# test_board.net
KiCad netlist of a schematic drawn in EAGLE
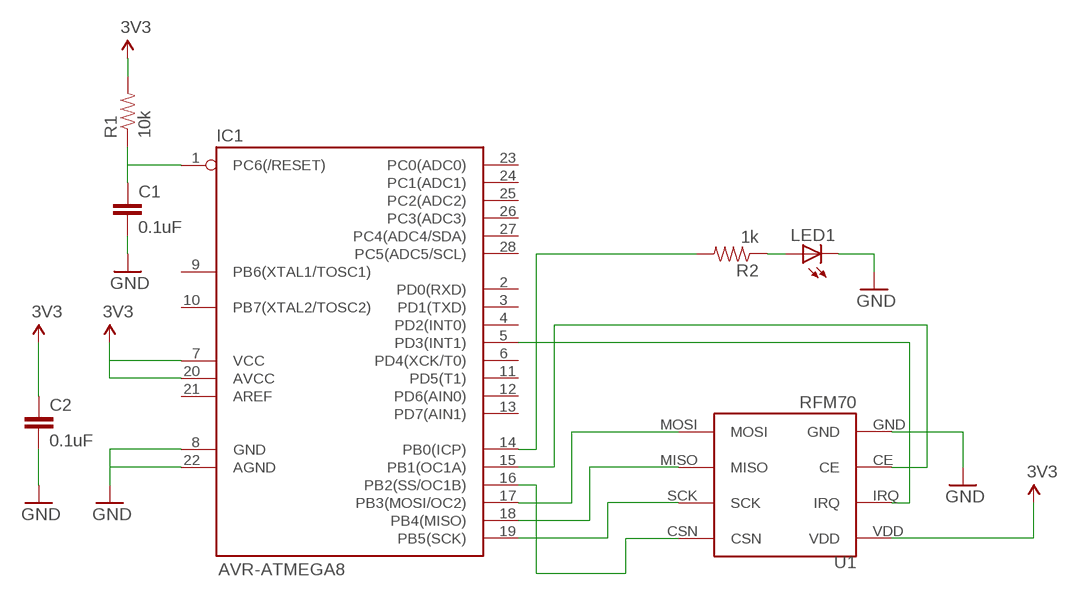
[diagram p0: schematic, sheet 1]

(export (version "E")
  (design (tool "Eeschema 10.0.6"))
  (components
    (comp (ref "C1")
      (value "0.1uF")
      (footprint "eagle-import:0603-CAP")
      (libsource (lib "eagle-import") (part "0.1UF-25V(+80/-20%)(0603)"))
    )
    (comp (ref "C2")
      (value "0.1uF")
      (footprint "eagle-import:0603-CAP")
      (libsource (lib "eagle-import") (part "0.1UF-25V(+80/-20%)(0603)"))
    )
    (comp (ref "IC1")
      (value "AVR-ATMEGA8")
      (footprint "eagle-import:DIL28-3")
      (libsource (lib "eagle-import") (part "AVR-MEGA8-PPTH"))
    )
    (comp (ref "LED1")
      (value "LED5MM")
      (footprint "eagle-import:LED5MM")
      (libsource (lib "eagle-import") (part "LED5MM"))
    )
    (comp (ref "R1")
      (value "10k")
      (footprint "eagle-import:0805")
      (libsource (lib "eagle-import") (part "0.75OHM-1/4W-1%(0805)"))
    )
    (comp (ref "R2")
      (value "1k")
      (footprint "eagle-import:0805")
      (libsource (lib "eagle-import") (part "0.75OHM-1/4W-1%(0805)"))
    )
    (comp (ref "U1")
      (value "RFM70")
      (footprint "eagle-import:RFM70")
      (libsource (lib "eagle-import") (part "RFM70"))
    )
  )
  (nets
    (net (code "1") (name "3V3") (class "Default")
      (node (ref "C2") (pin "1") (pinfunction "1_1") (pintype "passive"))
      (node (ref "IC1") (pin "20") (pinfunction "AVCC_20") (pintype "bidirectional"))
      (node (ref "IC1") (pin "7") (pinfunction "VCC_7") (pintype "bidirectional"))
      (node (ref "R1") (pin "2") (pinfunction "2_2") (pintype "passive"))
      (node (ref "U1") (pin "VDD") (pinfunction "VDD_VDD") (pintype "power_in"))
    )
    (net (code "2") (name "GND") (class "Default")
      (node (ref "C1") (pin "2") (pinfunction "2_2") (pintype "passive"))
      (node (ref "C2") (pin "2") (pinfunction "2_2") (pintype "passive"))
      (node (ref "IC1") (pin "22") (pinfunction "AGND_22") (pintype "bidirectional"))
      (node (ref "IC1") (pin "8") (pinfunction "GND_8") (pintype "bidirectional"))
      (node (ref "LED1") (pin "K") (pinfunction "C_K") (pintype "passive"))
      (node (ref "U1") (pin "GND") (pinfunction "GND_GND") (pintype "power_in"))
    )
    (net (code "3") (name "Net-(IC1-PB0(ICP))") (class "Default")
      (node (ref "IC1") (pin "14") (pinfunction "PB0(ICP)_14") (pintype "bidirectional"))
      (node (ref "R2") (pin "2") (pinfunction "2_2") (pintype "passive"))
    )
    (net (code "4") (name "Net-(IC1-PB1(OC1A))") (class "Default")
      (node (ref "IC1") (pin "15") (pinfunction "PB1(OC1A)_15") (pintype "bidirectional"))
      (node (ref "U1") (pin "CE") (pinfunction "CE_CE") (pintype "input"))
    )
    (net (code "5") (name "Net-(IC1-PB2(SS{slash}OC1B))") (class "Default")
      (node (ref "IC1") (pin "16") (pinfunction "PB2(SS/OC1B)_16") (pintype "bidirectional"))
      (node (ref "U1") (pin "CSN") (pinfunction "CSN_CSN") (pintype "input"))
    )
    (net (code "6") (name "Net-(IC1-PB3(MOSI{slash}OC2))") (class "Default")
      (node (ref "IC1") (pin "17") (pinfunction "PB3(MOSI/OC2)_17") (pintype "bidirectional"))
      (node (ref "U1") (pin "MOSI") (pinfunction "MOSI_MOSI") (pintype "input"))
    )
    (net (code "7") (name "Net-(IC1-PB4(MISO))") (class "Default")
      (node (ref "IC1") (pin "18") (pinfunction "PB4(MISO)_18") (pintype "bidirectional"))
      (node (ref "U1") (pin "MISO") (pinfunction "MISO_MISO") (pintype "output"))
    )
    (net (code "8") (name "Net-(IC1-PB5(SCK))") (class "Default")
      (node (ref "IC1") (pin "19") (pinfunction "PB5(SCK)_19") (pintype "bidirectional"))
      (node (ref "U1") (pin "SCK") (pinfunction "SCK_SCK") (pintype "input"))
    )
    (net (code "9") (name "Net-(IC1-PC6({slash}RESET))") (class "Default")
      (node (ref "C1") (pin "1") (pinfunction "1_1") (pintype "passive"))
      (node (ref "IC1") (pin "1") (pinfunction "PC6(/RESET)_1") (pintype "bidirectional"))
      (node (ref "R1") (pin "1") (pinfunction "1_1") (pintype "passive"))
    )
    (net (code "10") (name "Net-(IC1-PD3(INT1))") (class "Default")
      (node (ref "IC1") (pin "5") (pinfunction "PD3(INT1)_5") (pintype "bidirectional"))
      (node (ref "U1") (pin "IRQ") (pinfunction "IRQ_IRQ") (pintype "output"))
    )
    (net (code "11") (name "Net-(LED1-PadA)") (class "Default")
      (node (ref "LED1") (pin "A") (pinfunction "A_A") (pintype "passive"))
      (node (ref "R2") (pin "1") (pinfunction "1_1") (pintype "passive"))
    )
    (net (code "12") (name "unconnected-(IC1-AREF-Pad21)") (class "Default")
      (node (ref "IC1") (pin "21") (pinfunction "AREF_21") (pintype "bidirectional"))
    )
    (net (code "13") (name "unconnected-(IC1-PB6(XTAL1{slash}TOSC1)-Pad9)") (class "Default")
      (node (ref "IC1") (pin "9") (pinfunction "PB6(XTAL1/TOSC1)_9") (pintype "bidirectional"))
    )
    (net (code "14") (name "unconnected-(IC1-PB7(XTAL2{slash}TOSC2)-Pad10)") (class "Default")
      (node (ref "IC1") (pin "10") (pinfunction "PB7(XTAL2/TOSC2)_10") (pintype "bidirectional"))
    )
    (net (code "15") (name "unconnected-(IC1-PC0(ADC0)-Pad23)") (class "Default")
      (node (ref "IC1") (pin "23") (pinfunction "PC0(ADC0)_23") (pintype "bidirectional"))
    )
    (net (code "16") (name "unconnected-(IC1-PC1(ADC1)-Pad24)") (class "Default")
      (node (ref "IC1") (pin "24") (pinfunction "PC1(ADC1)_24") (pintype "bidirectional"))
    )
    (net (code "17") (name "unconnected-(IC1-PC2(ADC2)-Pad25)") (class "Default")
      (node (ref "IC1") (pin "25") (pinfunction "PC2(ADC2)_25") (pintype "bidirectional"))
    )
    (net (code "18") (name "unconnected-(IC1-PC3(ADC3)-Pad26)") (class "Default")
      (node (ref "IC1") (pin "26") (pinfunction "PC3(ADC3)_26") (pintype "bidirectional"))
    )
    (net (code "19") (name "unconnected-(IC1-PC4(ADC4{slash}SDA)-Pad27)") (class "Default")
      (node (ref "IC1") (pin "27") (pinfunction "PC4(ADC4/SDA)_27") (pintype "bidirectional"))
    )
    (net (code "20") (name "unconnected-(IC1-PC5(ADC5{slash}SCL)-Pad28)") (class "Default")
      (node (ref "IC1") (pin "28") (pinfunction "PC5(ADC5/SCL)_28") (pintype "bidirectional"))
    )
    (net (code "21") (name "unconnected-(IC1-PD0(RXD)-Pad2)") (class "Default")
      (node (ref "IC1") (pin "2") (pinfunction "PD0(RXD)_2") (pintype "bidirectional"))
    )
    (net (code "22") (name "unconnected-(IC1-PD1(TXD)-Pad3)") (class "Default")
      (node (ref "IC1") (pin "3") (pinfunction "PD1(TXD)_3") (pintype "bidirectional"))
    )
    (net (code "23") (name "unconnected-(IC1-PD2(INT0)-Pad4)") (class "Default")
      (node (ref "IC1") (pin "4") (pinfunction "PD2(INT0)_4") (pintype "bidirectional"))
    )
    (net (code "24") (name "unconnected-(IC1-PD4(XCK{slash}T0)-Pad6)") (class "Default")
      (node (ref "IC1") (pin "6") (pinfunction "PD4(XCK/T0)_6") (pintype "bidirectional"))
    )
    (net (code "25") (name "unconnected-(IC1-PD5(T1)-Pad11)") (class "Default")
      (node (ref "IC1") (pin "11") (pinfunction "PD5(T1)_11") (pintype "bidirectional"))
    )
    (net (code "26") (name "unconnected-(IC1-PD6(AIN0)-Pad12)") (class "Default")
      (node (ref "IC1") (pin "12") (pinfunction "PD6(AIN0)_12") (pintype "bidirectional"))
    )
    (net (code "27") (name "unconnected-(IC1-PD7(AIN1)-Pad13)") (class "Default")
      (node (ref "IC1") (pin "13") (pinfunction "PD7(AIN1)_13") (pintype "bidirectional"))
    )
  )
)
